# mm_robot_pcb_v5.net
KiCad netlist of a schematic drawn in EAGLE
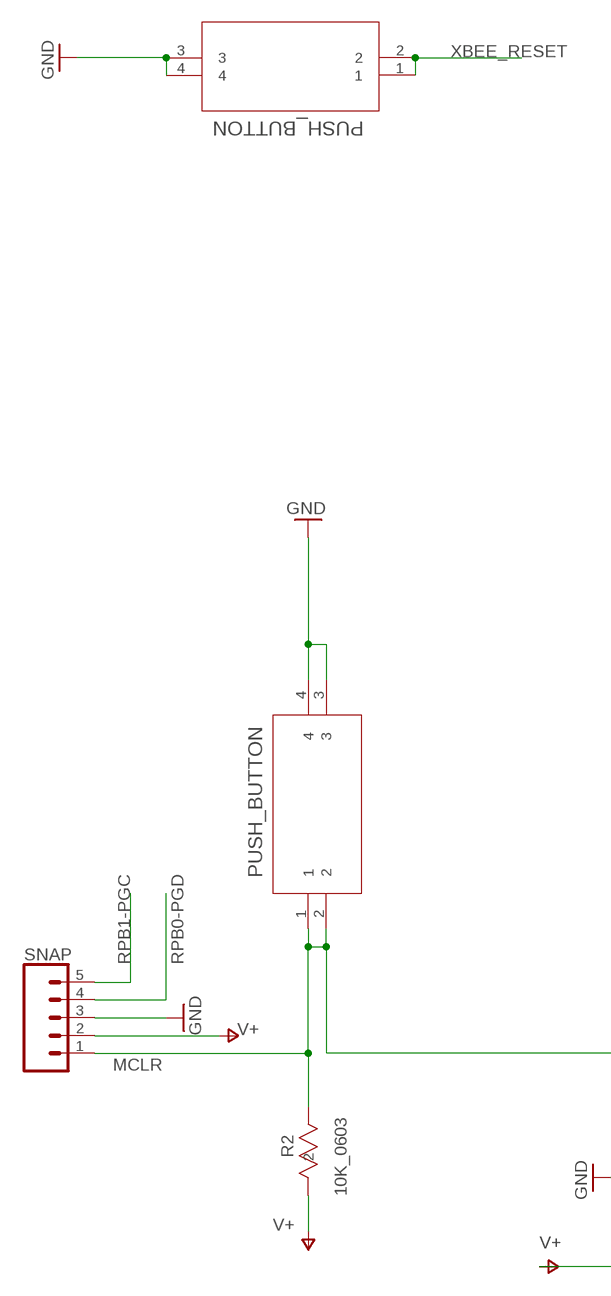
[diagram p0: schematic, sheet 1, part 1 of 2]
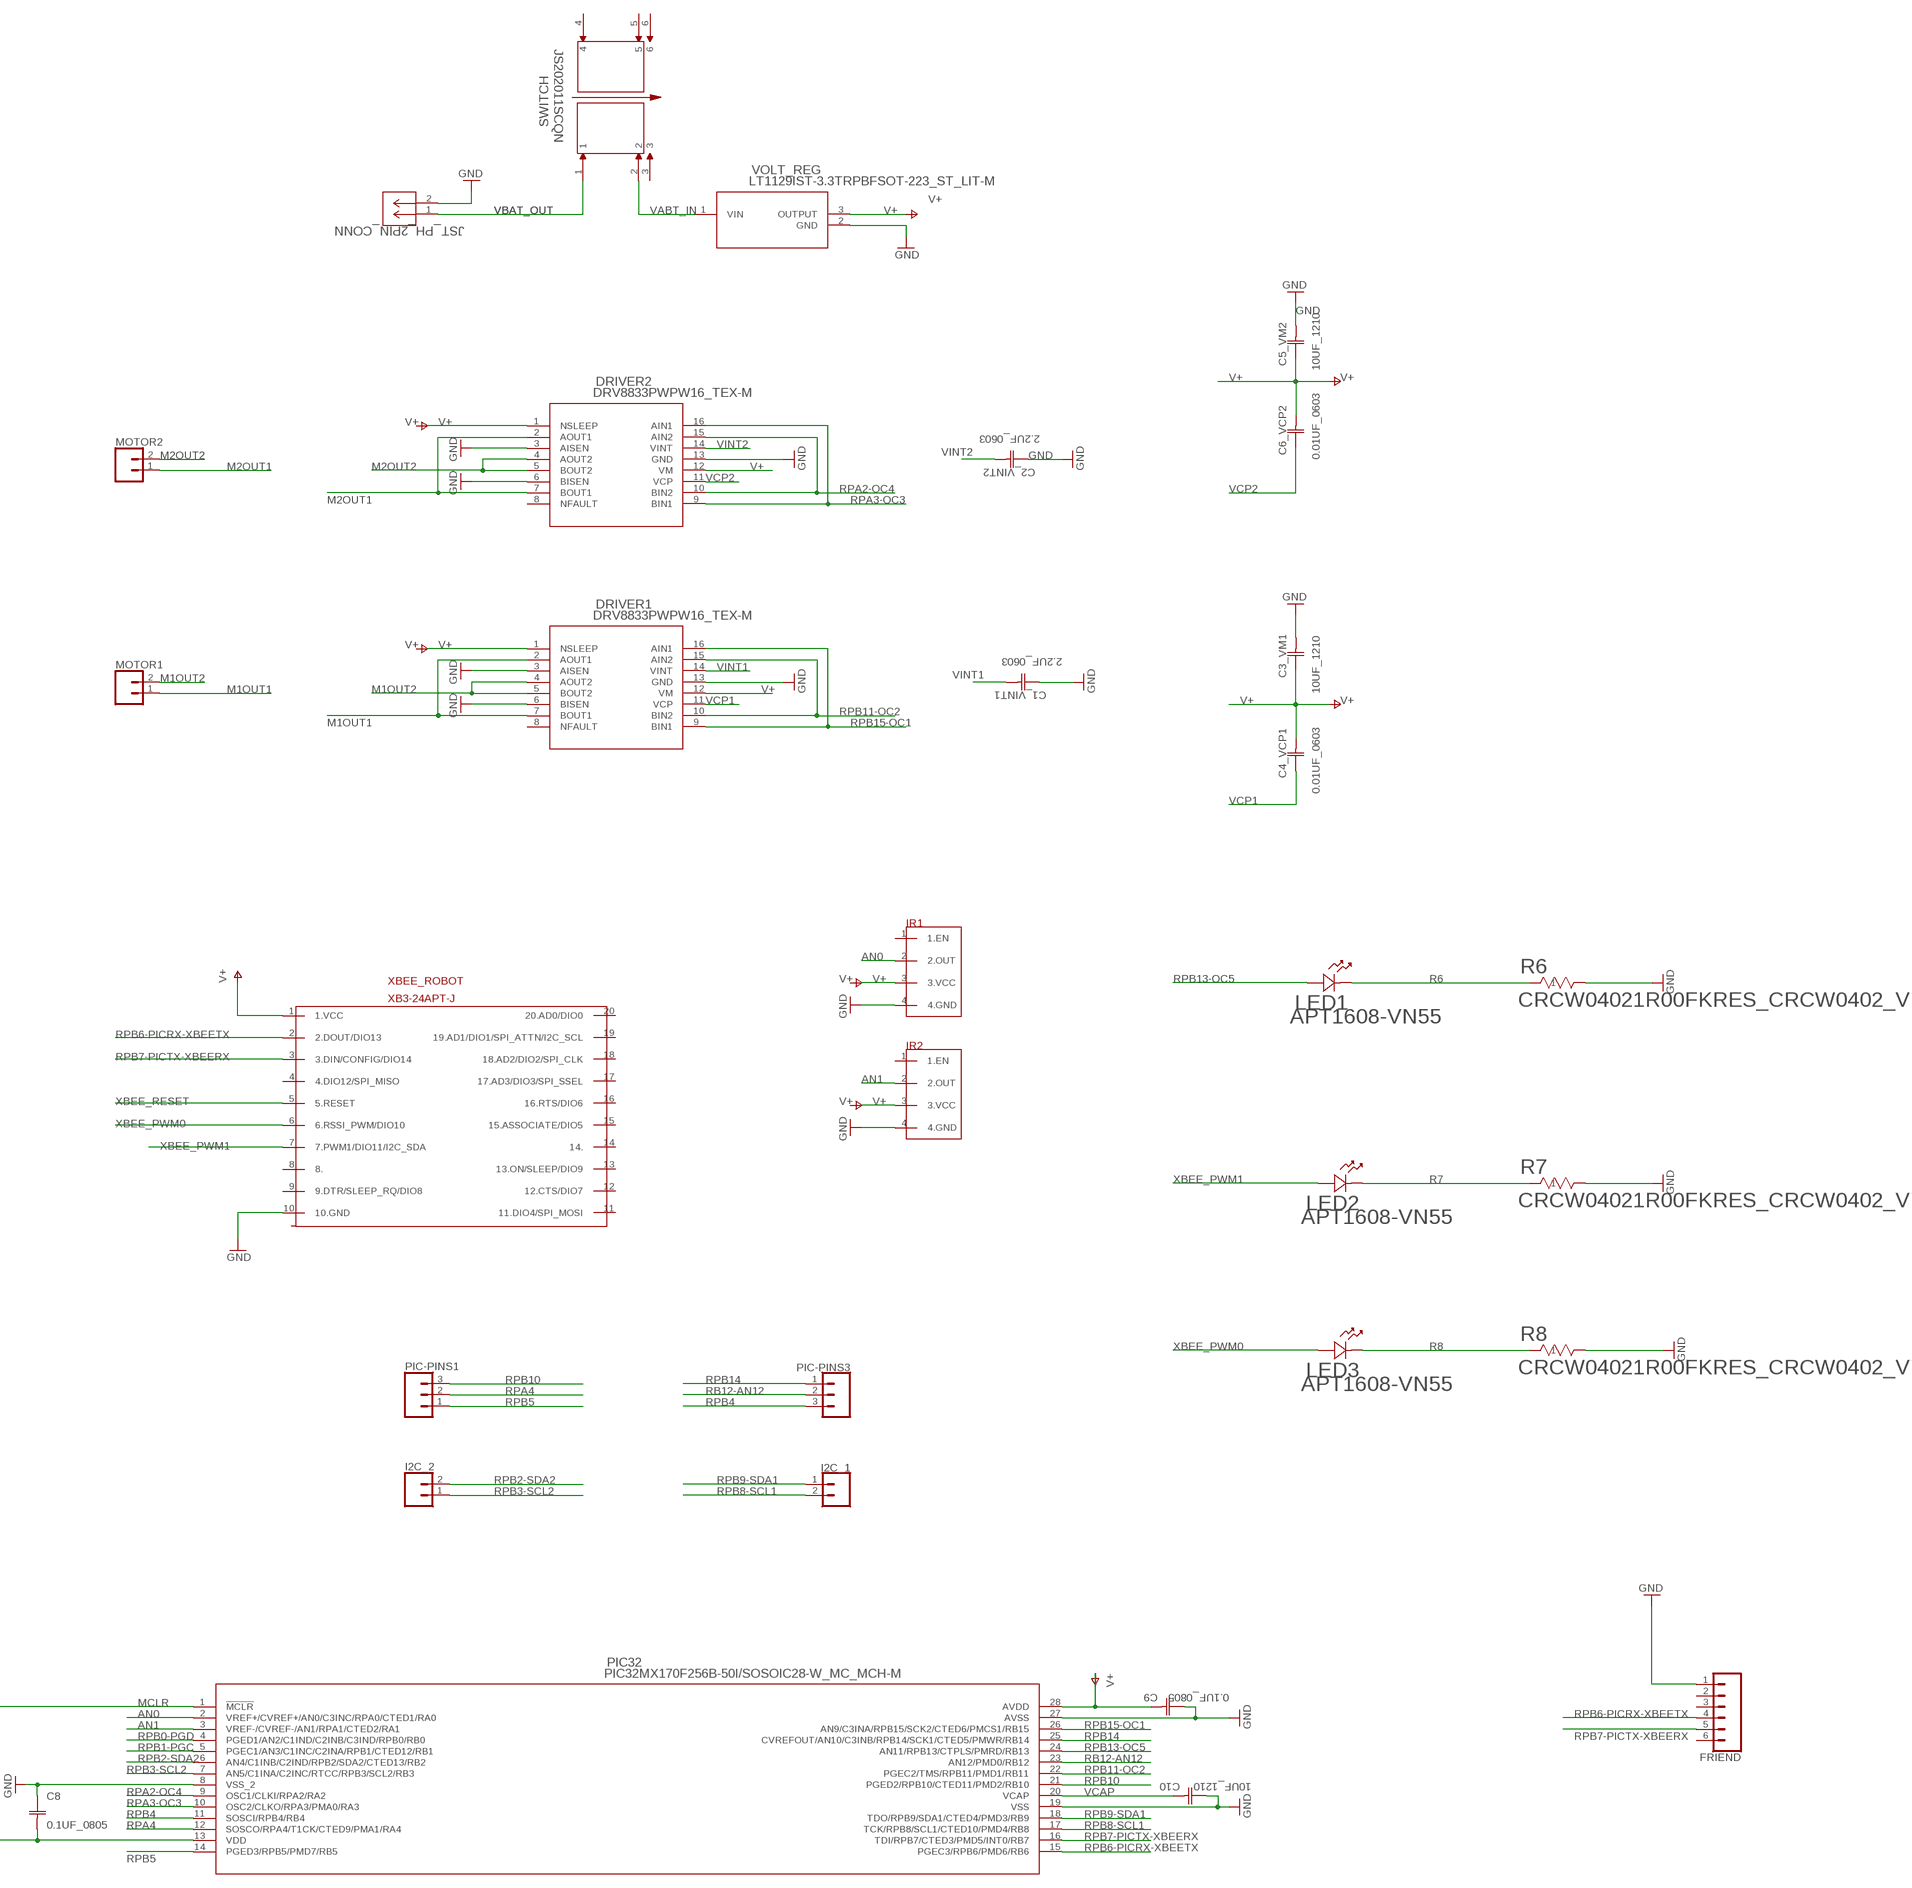
[diagram p1: schematic, sheet 1, part 2 of 2]

(export (version "E")
  (design (tool "Eeschema 10.0.6"))
  (components
    (comp (ref "C1_VINT1")
      (value "2.2UF_0603")
      (footprint "eagle-import:CAP_CL10_SAM-M")
      (fields
        (field (name "MANUFACTURER_PART_NUMBER") "CL10A225KP8NNNC")
        (field (name "COPYRIGHT") "Copyright (C) 2021 Ultra Librarian. All rights reserved.")
      )
      (libsource (lib "eagle-import") (part "CL10A225KP8NNNCCAP_CL10_SAM-M"))
    )
    (comp (ref "C2_VINT2")
      (value "2.2UF_0603")
      (footprint "eagle-import:CAP_CL10_SAM-M")
      (fields
        (field (name "MANUFACTURER_PART_NUMBER") "CL10A225KP8NNNC")
        (field (name "COPYRIGHT") "Copyright (C) 2021 Ultra Librarian. All rights reserved.")
      )
      (libsource (lib "eagle-import") (part "CL10A225KP8NNNCCAP_CL10_SAM-M"))
    )
    (comp (ref "C3_VM1")
      (value "10UF_1210")
      (footprint "eagle-import:CAP_TPS_B_AVX-M")
      (fields
        (field (name "MANUFACTURER_PART_NUMBER") "TPSB106K016R0500")
        (field (name "COPYRIGHT") "Copyright (C) 2021 Ultra Librarian. All rights reserved.")
      )
      (libsource (lib "eagle-import") (part "TPSB106K016R0500CAP_TPS_B_AVX-M"))
    )
    (comp (ref "C4_VCP1")
      (value "0.01UF_0603")
      (footprint "eagle-import:CAP_01UF_0603_X7R_G_AVX")
      (libsource (lib "eagle-import") (part "01UF_CAP"))
    )
    (comp (ref "C5_VM2")
      (value "10UF_1210")
      (footprint "eagle-import:CAP_TPS_B_AVX-M")
      (fields
        (field (name "MANUFACTURER_PART_NUMBER") "TPSB106K016R0500")
        (field (name "COPYRIGHT") "Copyright (C) 2021 Ultra Librarian. All rights reserved.")
      )
      (libsource (lib "eagle-import") (part "TPSB106K016R0500CAP_TPS_B_AVX-M"))
    )
    (comp (ref "C6_VCP2")
      (value "0.01UF_0603")
      (footprint "eagle-import:CAP_01UF_0603_X7R_G_AVX")
      (libsource (lib "eagle-import") (part "01UF_CAP"))
    )
    (comp (ref "C8")
      (value "0.1UF_0805")
      (footprint "eagle-import:CAP_C2012X7R2A104K125AA_TDK-M")
      (fields
        (field (name "MANUFACTURER_PART_NUMBER") "C2012X7R2A104K125AA")
        (field (name "COPYRIGHT") "Copyright (C) 2021 Ultra Librarian. All rights reserved.")
      )
      (libsource (lib "eagle-import") (part "C2012X7R2A104K125AACAP_C2012X7R2A104K125AA_TDK-M"))
    )
    (comp (ref "C9")
      (value "0.1UF_0805")
      (footprint "eagle-import:CAP_C2012X7R2A104K125AA_TDK-M")
      (fields
        (field (name "MANUFACTURER_PART_NUMBER") "C2012X7R2A104K125AA")
        (field (name "COPYRIGHT") "Copyright (C) 2021 Ultra Librarian. All rights reserved.")
      )
      (libsource (lib "eagle-import") (part "C2012X7R2A104K125AACAP_C2012X7R2A104K125AA_TDK-M"))
    )
    (comp (ref "C10")
      (value "10UF_1210")
      (footprint "eagle-import:CAP_TPS_B_AVX-M")
      (fields
        (field (name "MANUFACTURER_PART_NUMBER") "TPSB106K016R0500")
        (field (name "COPYRIGHT") "Copyright (C) 2021 Ultra Librarian. All rights reserved.")
      )
      (libsource (lib "eagle-import") (part "TPSB106K016R0500CAP_TPS_B_AVX-M"))
    )
    (comp (ref "DRIVER1")
      (value "DRV8833PWPW16_TEX-M")
      (footprint "eagle-import:PW16_TEX-M")
      (fields
        (field (name "MANUFACTURER_PART_NUMBER") "DRV8833PW")
        (field (name "COPYRIGHT") "Copyright (C) 2021 Ultra Librarian. All rights reserved.")
      )
      (libsource (lib "eagle-import") (part "DRV8833PWPW16_TEX-M"))
    )
    (comp (ref "DRIVER2")
      (value "DRV8833PWPW16_TEX-M")
      (footprint "eagle-import:PW16_TEX-M")
      (fields
        (field (name "MANUFACTURER_PART_NUMBER") "DRV8833PW")
        (field (name "COPYRIGHT") "Copyright (C) 2021 Ultra Librarian. All rights reserved.")
      )
      (libsource (lib "eagle-import") (part "DRV8833PWPW16_TEX-M"))
    )
    (comp (ref "FRIEND")
      (value "CONN_06NO_SILK_FEMALE_PTH")
      (footprint "eagle-import:1X06_NO_SILK")
      (libsource (lib "eagle-import") (part "CONN_06NO_SILK_FEMALE_PTH"))
    )
    (comp (ref "I2C_1")
      (value "CONN_02")
      (footprint "eagle-import:1X02")
      (libsource (lib "eagle-import") (part "CONN_02"))
    )
    (comp (ref "I2C_2")
      (value "CONN_02")
      (footprint "eagle-import:1X02")
      (libsource (lib "eagle-import") (part "CONN_02"))
    )
    (comp (ref "IR1")
      (value "GP2Y0A60SZLF")
      (footprint "eagle-import:1X04")
      (libsource (lib "eagle-import") (part "GP2Y0A60SZLF"))
    )
    (comp (ref "IR2")
      (value "GP2Y0A60SZLF")
      (footprint "eagle-import:1X04")
      (libsource (lib "eagle-import") (part "GP2Y0A60SZLF"))
    )
    (comp (ref "JST_PH_2PIN_CONN")
      (value "1769")
      (footprint "eagle-import:CONN_1769_ADA")
      (fields (field (name "COPYRIGHT") "Copyright (C) 2021 Ultra Librarian. All rights reserved."))
      (libsource (lib "eagle-import") (part "1769"))
    )
    (comp (ref "LED1")
      (value "APT1608-VN55")
      (footprint "eagle-import:LED_APT1608_KNB")
      (fields (field (name "COPYRIGHT") "Copyright (C) 2021 Ultra Librarian. All rights reserved."))
      (libsource (lib "eagle-import") (part "APT1608-VN55"))
    )
    (comp (ref "LED2")
      (value "APT1608-VN55")
      (footprint "eagle-import:LED_APT1608_KNB")
      (fields (field (name "COPYRIGHT") "Copyright (C) 2021 Ultra Librarian. All rights reserved."))
      (libsource (lib "eagle-import") (part "APT1608-VN55"))
    )
    (comp (ref "LED3")
      (value "APT1608-VN55")
      (footprint "eagle-import:LED_APT1608_KNB")
      (fields (field (name "COPYRIGHT") "Copyright (C) 2021 Ultra Librarian. All rights reserved."))
      (libsource (lib "eagle-import") (part "APT1608-VN55"))
    )
    (comp (ref "MOTOR1")
      (value "CONN_02")
      (footprint "eagle-import:1X02")
      (libsource (lib "eagle-import") (part "CONN_02"))
    )
    (comp (ref "MOTOR2")
      (value "CONN_02")
      (footprint "eagle-import:1X02")
      (libsource (lib "eagle-import") (part "CONN_02"))
    )
    (comp (ref "PIC-PINS1")
      (value "455-1750-1-ND")
      (footprint "eagle-import:1X03")
      (libsource (lib "eagle-import") (part "CONN_03"))
    )
    (comp (ref "PIC-PINS3")
      (value "455-1750-1-ND")
      (footprint "eagle-import:1X03")
      (libsource (lib "eagle-import") (part "CONN_03"))
    )
    (comp (ref "PIC32")
      (value "PIC32MX170F256B-50I/SOSOIC28-W_MC_MCH-M")
      (footprint "eagle-import:SOIC28-W_MC_MCH-M")
      (fields
        (field (name "MANUFACTURER_PART_NUMBER") "PIC32MX170F256B-50I/SO")
        (field (name "COPYRIGHT") "Copyright (C) 2021 Ultra Librarian. All rights reserved.")
      )
      (libsource (lib "eagle-import") (part "PIC32MX170F256B-50I/SOSOIC28-W_MC_MCH-M"))
    )
    (comp (ref "PIC_PB")
      (value "PUSH_BUTTON")
      (footprint "eagle-import:SMT_FS-M")
      (fields
        (field (name "MANUFACTURER_PART_NUMBER") "PTS526 SK15 SMTR2 LFS")
        (field (name "COPYRIGHT") "Copyright (C) 2021 Ultra Librarian. All rights reserved.")
      )
      (libsource (lib "eagle-import") (part "PTS526_SK15_SMTR2_LFSSMT_FS-M"))
    )
    (comp (ref "R2")
      (value "10K_0603")
      (footprint "eagle-import:RES0603_CRG_TYCO_TYC-M")
      (fields
        (field (name "MANUFACTURER_PART_NUMBER") "CRG0603F10K")
        (field (name "COPYRIGHT") "Copyright (C) 2021 Ultra Librarian. All rights reserved.")
      )
      (libsource (lib "eagle-import") (part "CRG0603F10KRES0603_CRG_TYCO_TYC-M"))
    )
    (comp (ref "R6")
      (value "CRCW04021R00FKRES_CRCW0402_VIS-M")
      (footprint "eagle-import:RES_CRCW0402_VIS-M")
      (fields
        (field (name "MANUFACTURER_PART_NUMBER") "CRCW04021R00FK")
        (field (name "COPYRIGHT") "Copyright (C) 2021 Ultra Librarian. All rights reserved.")
      )
      (libsource (lib "eagle-import") (part "CRCW04021R00FKRES_CRCW0402_VIS-M"))
    )
    (comp (ref "R7")
      (value "CRCW04021R00FKRES_CRCW0402_VIS-M")
      (footprint "eagle-import:RES_CRCW0402_VIS-M")
      (fields
        (field (name "MANUFACTURER_PART_NUMBER") "CRCW04021R00FK")
        (field (name "COPYRIGHT") "Copyright (C) 2021 Ultra Librarian. All rights reserved.")
      )
      (libsource (lib "eagle-import") (part "CRCW04021R00FKRES_CRCW0402_VIS-M"))
    )
    (comp (ref "R8")
      (value "CRCW04021R00FKRES_CRCW0402_VIS-M")
      (footprint "eagle-import:RES_CRCW0402_VIS-M")
      (fields
        (field (name "MANUFACTURER_PART_NUMBER") "CRCW04021R00FK")
        (field (name "COPYRIGHT") "Copyright (C) 2021 Ultra Librarian. All rights reserved.")
      )
      (libsource (lib "eagle-import") (part "CRCW04021R00FKRES_CRCW0402_VIS-M"))
    )
    (comp (ref "SNAP")
      (value "CONN_05")
      (footprint "eagle-import:1X05")
      (libsource (lib "eagle-import") (part "CONN_05"))
    )
    (comp (ref "SWITCH")
      (value "JS202011SCQN")
      (footprint "eagle-import:SW_JS202011SCQN")
      (fields (field (name "COPYRIGHT") "Copyright (C) 2021 Ultra Librarian. All rights reserved."))
      (libsource (lib "eagle-import") (part "JS202011SCQN"))
    )
    (comp (ref "VOLT_REG")
      (value "LT1129IST-3.3TRPBFSOT-223_ST_LIT-M")
      (footprint "eagle-import:SOT-223_ST_LIT-M")
      (fields
        (field (name "MANUFACTURER_PART_NUMBER") "LT1129IST-3.3#TRPBF")
        (field (name "COPYRIGHT") "Copyright (C) 2021 Ultra Librarian. All rights reserved.")
      )
      (libsource (lib "eagle-import") (part "LT1129IST-3.3TRPBFSOT-223_ST_LIT-M"))
    )
    (comp (ref "XBEE_PB")
      (value "PUSH_BUTTON")
      (footprint "eagle-import:SMT_FS-M")
      (fields
        (field (name "MANUFACTURER_PART_NUMBER") "PTS526 SK15 SMTR2 LFS")
        (field (name "COPYRIGHT") "Copyright (C) 2021 Ultra Librarian. All rights reserved.")
      )
      (libsource (lib "eagle-import") (part "PTS526_SK15_SMTR2_LFSSMT_FS-M"))
    )
    (comp (ref "XBEE_ROBOT")
      (value "XB3-24APT-J")
      (footprint "eagle-import:XB3-24APT-J")
      (libsource (lib "eagle-import") (part "XB3-24APT-J"))
    )
  )
  (nets
    (net (code "1") (name "/AN0") (class "Default")
      (node (ref "IR1") (pin "2") (pinfunction "2.OUT_2") (pintype "bidirectional"))
      (node (ref "PIC32") (pin "2") (pinfunction "VREF+/CVREF+/AN0/C3INC/RPA0/CTED1/RA0_2") (pintype "bidirectional"))
    )
    (net (code "2") (name "/AN1") (class "Default")
      (node (ref "IR2") (pin "2") (pinfunction "2.OUT_2") (pintype "bidirectional"))
      (node (ref "PIC32") (pin "3") (pinfunction "VREF-/CVREF-/AN1/RPA1/CTED2/RA1_3") (pintype "bidirectional"))
    )
    (net (code "3") (name "/M1OUT1") (class "Default")
      (node (ref "DRIVER1") (pin "2") (pinfunction "AOUT1_2") (pintype "output"))
      (node (ref "DRIVER1") (pin "7") (pinfunction "BOUT1_7") (pintype "output"))
      (node (ref "MOTOR1") (pin "1") (pinfunction "1_1") (pintype "passive"))
    )
    (net (code "4") (name "/M1OUT2") (class "Default")
      (node (ref "DRIVER1") (pin "4") (pinfunction "AOUT2_4") (pintype "output"))
      (node (ref "DRIVER1") (pin "5") (pinfunction "BOUT2_5") (pintype "output"))
      (node (ref "MOTOR1") (pin "2") (pinfunction "2_2") (pintype "passive"))
    )
    (net (code "5") (name "/M2OUT1") (class "Default")
      (node (ref "DRIVER2") (pin "2") (pinfunction "AOUT1_2") (pintype "output"))
      (node (ref "DRIVER2") (pin "7") (pinfunction "BOUT1_7") (pintype "output"))
      (node (ref "MOTOR2") (pin "1") (pinfunction "1_1") (pintype "passive"))
    )
    (net (code "6") (name "/M2OUT2") (class "Default")
      (node (ref "DRIVER2") (pin "4") (pinfunction "AOUT2_4") (pintype "output"))
      (node (ref "DRIVER2") (pin "5") (pinfunction "BOUT2_5") (pintype "output"))
      (node (ref "MOTOR2") (pin "2") (pinfunction "2_2") (pintype "passive"))
    )
    (net (code "7") (name "/MCLR") (class "Default")
      (node (ref "PIC32") (pin "1") (pinfunction "~{MCLR}_1") (pintype "bidirectional"))
      (node (ref "PIC_PB") (pin "1") (pinfunction "1_1") (pintype "passive"))
      (node (ref "PIC_PB") (pin "2") (pinfunction "2_2") (pintype "passive"))
      (node (ref "R2") (pin "1") (pinfunction "1_1") (pintype "passive"))
      (node (ref "SNAP") (pin "1") (pinfunction "1_1") (pintype "passive"))
    )
    (net (code "8") (name "/R6") (class "Default")
      (node (ref "LED1") (pin "1") (pinfunction "1_1") (pintype "passive"))
      (node (ref "R6") (pin "1") (pinfunction "1_1") (pintype "passive"))
    )
    (net (code "9") (name "/R7") (class "Default")
      (node (ref "LED2") (pin "1") (pinfunction "1_1") (pintype "passive"))
      (node (ref "R7") (pin "1") (pinfunction "1_1") (pintype "passive"))
    )
    (net (code "10") (name "/R8") (class "Default")
      (node (ref "LED3") (pin "1") (pinfunction "1_1") (pintype "passive"))
      (node (ref "R8") (pin "1") (pinfunction "1_1") (pintype "passive"))
    )
    (net (code "11") (name "/RB12-AN12") (class "Default")
      (node (ref "PIC-PINS3") (pin "2") (pinfunction "2_2") (pintype "passive"))
      (node (ref "PIC32") (pin "23") (pinfunction "AN12/PMD0/RB12_23") (pintype "bidirectional"))
    )
    (net (code "12") (name "/RPA2-OC4") (class "Default")
      (node (ref "DRIVER2") (pin "10") (pinfunction "BIN2_10") (pintype "input"))
      (node (ref "DRIVER2") (pin "15") (pinfunction "AIN2_15") (pintype "input"))
      (node (ref "PIC32") (pin "9") (pinfunction "OSC1/CLKI/RPA2/RA2_9") (pintype "bidirectional"))
    )
    (net (code "13") (name "/RPA3-OC3") (class "Default")
      (node (ref "DRIVER2") (pin "16") (pinfunction "AIN1_16") (pintype "input"))
      (node (ref "DRIVER2") (pin "9") (pinfunction "BIN1_9") (pintype "input"))
      (node (ref "PIC32") (pin "10") (pinfunction "OSC2/CLKO/RPA3/PMA0/RA3_10") (pintype "bidirectional"))
    )
    (net (code "14") (name "/RPA4") (class "Default")
      (node (ref "PIC-PINS1") (pin "2") (pinfunction "2_2") (pintype "passive"))
      (node (ref "PIC32") (pin "12") (pinfunction "SOSCO/RPA4/T1CK/CTED9/PMA1/RA4_12") (pintype "bidirectional"))
    )
    (net (code "15") (name "/RPB0-PGD") (class "Default")
      (node (ref "PIC32") (pin "4") (pinfunction "PGED1/AN2/C1IND/C2INB/C3IND/RPB0/RB0_4") (pintype "bidirectional"))
      (node (ref "SNAP") (pin "4") (pinfunction "4_4") (pintype "passive"))
    )
    (net (code "16") (name "/RPB1-PGC") (class "Default")
      (node (ref "PIC32") (pin "5") (pinfunction "PGEC1/AN3/C1INC/C2INA/RPB1/CTED12/RB1_5") (pintype "bidirectional"))
      (node (ref "SNAP") (pin "5") (pinfunction "5_5") (pintype "passive"))
    )
    (net (code "17") (name "/RPB2-SDA2") (class "Default")
      (node (ref "I2C_2") (pin "2") (pinfunction "2_2") (pintype "passive"))
      (node (ref "PIC32") (pin "6") (pinfunction "AN4/C1INB/C2IND/RPB2/SDA2/CTED13/RB2_6") (pintype "bidirectional"))
    )
    (net (code "18") (name "/RPB3-SCL2") (class "Default")
      (node (ref "I2C_2") (pin "1") (pinfunction "1_1") (pintype "passive"))
      (node (ref "PIC32") (pin "7") (pinfunction "AN5/C1INA/C2INC/RTCC/RPB3/SCL2/RB3_7") (pintype "bidirectional"))
    )
    (net (code "19") (name "/RPB4") (class "Default")
      (node (ref "PIC-PINS3") (pin "3") (pinfunction "3_3") (pintype "passive"))
      (node (ref "PIC32") (pin "11") (pinfunction "SOSCI/RPB4/RB4_11") (pintype "bidirectional"))
    )
    (net (code "20") (name "/RPB5") (class "Default")
      (node (ref "PIC-PINS1") (pin "1") (pinfunction "1_1") (pintype "passive"))
      (node (ref "PIC32") (pin "14") (pinfunction "PGED3/RPB5/PMD7/RB5_14") (pintype "bidirectional"))
    )
    (net (code "21") (name "/RPB6-PICRX-XBEETX") (class "Default")
      (node (ref "FRIEND") (pin "4") (pinfunction "4_4") (pintype "passive"))
      (node (ref "PIC32") (pin "15") (pinfunction "PGEC3/RPB6/PMD6/RB6_15") (pintype "bidirectional"))
      (node (ref "XBEE_ROBOT") (pin "2") (pinfunction "2.DOUT/DIO13_2") (pintype "bidirectional"))
    )
    (net (code "22") (name "/RPB7-PICTX-XBEERX") (class "Default")
      (node (ref "FRIEND") (pin "5") (pinfunction "5_5") (pintype "passive"))
      (node (ref "PIC32") (pin "16") (pinfunction "TDI/RPB7/CTED3/PMD5/INT0/RB7_16") (pintype "bidirectional"))
      (node (ref "XBEE_ROBOT") (pin "3") (pinfunction "3.DIN/CONFIG/DIO14_3") (pintype "bidirectional"))
    )
    (net (code "23") (name "/RPB8-SCL1") (class "Default")
      (node (ref "I2C_1") (pin "2") (pinfunction "2_2") (pintype "passive"))
      (node (ref "PIC32") (pin "17") (pinfunction "TCK/RPB8/SCL1/CTED10/PMD4/RB8_17") (pintype "bidirectional"))
    )
    (net (code "24") (name "/RPB9-SDA1") (class "Default")
      (node (ref "I2C_1") (pin "1") (pinfunction "1_1") (pintype "passive"))
      (node (ref "PIC32") (pin "18") (pinfunction "TDO/RPB9/SDA1/CTED4/PMD3/RB9_18") (pintype "bidirectional"))
    )
    (net (code "25") (name "/RPB10") (class "Default")
      (node (ref "PIC-PINS1") (pin "3") (pinfunction "3_3") (pintype "passive"))
      (node (ref "PIC32") (pin "21") (pinfunction "PGED2/RPB10/CTED11/PMD2/RB10_21") (pintype "bidirectional"))
    )
    (net (code "26") (name "/RPB11-OC2") (class "Default")
      (node (ref "DRIVER1") (pin "10") (pinfunction "BIN2_10") (pintype "input"))
      (node (ref "DRIVER1") (pin "15") (pinfunction "AIN2_15") (pintype "input"))
      (node (ref "PIC32") (pin "22") (pinfunction "PGEC2/TMS/RPB11/PMD1/RB11_22") (pintype "bidirectional"))
    )
    (net (code "27") (name "/RPB13-OC5") (class "Default")
      (node (ref "LED1") (pin "2") (pinfunction "2_2") (pintype "passive"))
      (node (ref "PIC32") (pin "24") (pinfunction "AN11/RPB13/CTPLS/PMRD/RB13_24") (pintype "bidirectional"))
    )
    (net (code "28") (name "/RPB14") (class "Default")
      (node (ref "PIC-PINS3") (pin "1") (pinfunction "1_1") (pintype "passive"))
      (node (ref "PIC32") (pin "25") (pinfunction "CVREFOUT/AN10/C3INB/RPB14/SCK1/CTED5/PMWR/RB14_25") (pintype "bidirectional"))
    )
    (net (code "29") (name "/RPB15-OC1") (class "Default")
      (node (ref "DRIVER1") (pin "16") (pinfunction "AIN1_16") (pintype "input"))
      (node (ref "DRIVER1") (pin "9") (pinfunction "BIN1_9") (pintype "input"))
      (node (ref "PIC32") (pin "26") (pinfunction "AN9/C3INA/RPB15/SCK2/CTED6/PMCS1/RB15_26") (pintype "bidirectional"))
    )
    (net (code "30") (name "/VABT_IN") (class "Default")
      (node (ref "SWITCH") (pin "2") (pinfunction "2_2") (pintype "passive"))
      (node (ref "VOLT_REG") (pin "1") (pinfunction "VIN_1") (pintype "input"))
    )
    (net (code "31") (name "/VBAT_OUT") (class "Default")
      (node (ref "JST_PH_2PIN_CONN") (pin "1") (pinfunction "1_1") (pintype "passive"))
      (node (ref "SWITCH") (pin "1") (pinfunction "1_1") (pintype "passive"))
    )
    (net (code "32") (name "/VCAP") (class "Default")
      (node (ref "C10") (pin "2") (pinfunction "12_2") (pintype "passive"))
      (node (ref "PIC32") (pin "20") (pinfunction "VCAP_20") (pintype "power_in"))
    )
    (net (code "33") (name "/VCP1") (class "Default")
      (node (ref "C4_VCP1") (pin "1") (pinfunction "1_1") (pintype "passive"))
      (node (ref "DRIVER1") (pin "11") (pinfunction "VCP_11") (pintype "bidirectional"))
    )
    (net (code "34") (name "/VCP2") (class "Default")
      (node (ref "C6_VCP2") (pin "1") (pinfunction "1_1") (pintype "passive"))
      (node (ref "DRIVER2") (pin "11") (pinfunction "VCP_11") (pintype "bidirectional"))
    )
    (net (code "35") (name "/VINT1") (class "Default")
      (node (ref "C1_VINT1") (pin "2") (pinfunction "2_2") (pintype "passive"))
      (node (ref "DRIVER1") (pin "14") (pinfunction "VINT_14") (pintype "passive"))
    )
    (net (code "36") (name "/VINT2") (class "Default")
      (node (ref "C2_VINT2") (pin "2") (pinfunction "2_2") (pintype "passive"))
      (node (ref "DRIVER2") (pin "14") (pinfunction "VINT_14") (pintype "passive"))
    )
    (net (code "37") (name "/XBEE_PWM0") (class "Default")
      (node (ref "LED3") (pin "2") (pinfunction "2_2") (pintype "passive"))
      (node (ref "XBEE_ROBOT") (pin "6") (pinfunction "6.RSSI_PWM/DIO10_6") (pintype "bidirectional"))
    )
    (net (code "38") (name "/XBEE_PWM1") (class "Default")
      (node (ref "LED2") (pin "2") (pinfunction "2_2") (pintype "passive"))
      (node (ref "XBEE_ROBOT") (pin "7") (pinfunction "7.PWM1/DIO11/I2C_SDA_7") (pintype "bidirectional"))
    )
    (net (code "39") (name "/XBEE_RESET") (class "Default")
      (node (ref "XBEE_PB") (pin "1") (pinfunction "1_1") (pintype "passive"))
      (node (ref "XBEE_PB") (pin "2") (pinfunction "2_2") (pintype "passive"))
      (node (ref "XBEE_ROBOT") (pin "5") (pinfunction "5.RESET_5") (pintype "bidirectional"))
    )
    (net (code "40") (name "GND") (class "Default")
      (node (ref "C10") (pin "1") (pinfunction "11_1") (pintype "passive"))
      (node (ref "C1_VINT1") (pin "1") (pinfunction "1_1") (pintype "passive"))
      (node (ref "C2_VINT2") (pin "1") (pinfunction "1_1") (pintype "passive"))
      (node (ref "C3_VM1") (pin "2") (pinfunction "12_2") (pintype "passive"))
      (node (ref "C5_VM2") (pin "2") (pinfunction "12_2") (pintype "passive"))
      (node (ref "C8") (pin "1") (pinfunction "1_1") (pintype "passive"))
      (node (ref "C9") (pin "1") (pinfunction "1_1") (pintype "passive"))
      (node (ref "DRIVER1") (pin "13") (pinfunction "GND_13") (pintype "power_in"))
      (node (ref "DRIVER1") (pin "3") (pinfunction "AISEN_3") (pintype "bidirectional"))
      (node (ref "DRIVER1") (pin "6") (pinfunction "BISEN_6") (pintype "bidirectional"))
      (node (ref "DRIVER2") (pin "13") (pinfunction "GND_13") (pintype "power_in"))
      (node (ref "DRIVER2") (pin "3") (pinfunction "AISEN_3") (pintype "bidirectional"))
      (node (ref "DRIVER2") (pin "6") (pinfunction "BISEN_6") (pintype "bidirectional"))
      (node (ref "FRIEND") (pin "1") (pinfunction "1_1") (pintype "passive"))
      (node (ref "IR1") (pin "4") (pinfunction "4.GND_4") (pintype "bidirectional"))
      (node (ref "IR2") (pin "4") (pinfunction "4.GND_4") (pintype "bidirectional"))
      (node (ref "JST_PH_2PIN_CONN") (pin "2") (pinfunction "2_2") (pintype "passive"))
      (node (ref "PIC32") (pin "19") (pinfunction "VSS_19") (pintype "power_in"))
      (node (ref "PIC32") (pin "27") (pinfunction "AVSS_27") (pintype "power_in"))
      (node (ref "PIC32") (pin "8") (pinfunction "VSS_2_8") (pintype "power_in"))
      (node (ref "PIC_PB") (pin "3") (pinfunction "3_3") (pintype "passive"))
      (node (ref "PIC_PB") (pin "4") (pinfunction "4_4") (pintype "passive"))
      (node (ref "R6") (pin "2") (pinfunction "2_2") (pintype "passive"))
      (node (ref "R7") (pin "2") (pinfunction "2_2") (pintype "passive"))
      (node (ref "R8") (pin "2") (pinfunction "2_2") (pintype "passive"))
      (node (ref "SNAP") (pin "3") (pinfunction "3_3") (pintype "passive"))
      (node (ref "VOLT_REG") (pin "2") (pinfunction "GND_2") (pintype "power_in"))
      (node (ref "XBEE_PB") (pin "3") (pinfunction "3_3") (pintype "passive"))
      (node (ref "XBEE_PB") (pin "4") (pinfunction "4_4") (pintype "passive"))
      (node (ref "XBEE_ROBOT") (pin "10") (pinfunction "10.GND_10") (pintype "bidirectional"))
    )
    (net (code "41") (name "V+") (class "Default")
      (node (ref "C3_VM1") (pin "1") (pinfunction "11_1") (pintype "passive"))
      (node (ref "C4_VCP1") (pin "2") (pinfunction "2_2") (pintype "passive"))
      (node (ref "C5_VM2") (pin "1") (pinfunction "11_1") (pintype "passive"))
      (node (ref "C6_VCP2") (pin "2") (pinfunction "2_2") (pintype "passive"))
      (node (ref "C8") (pin "2") (pinfunction "2_2") (pintype "passive"))
      (node (ref "C9") (pin "2") (pinfunction "2_2") (pintype "passive"))
      (node (ref "DRIVER1") (pin "1") (pinfunction "NSLEEP_1") (pintype "input"))
      (node (ref "DRIVER1") (pin "12") (pinfunction "VM_12") (pintype "power_in"))
      (node (ref "DRIVER2") (pin "1") (pinfunction "NSLEEP_1") (pintype "input"))
      (node (ref "DRIVER2") (pin "12") (pinfunction "VM_12") (pintype "power_in"))
      (node (ref "IR1") (pin "3") (pinfunction "3.VCC_3") (pintype "bidirectional"))
      (node (ref "IR2") (pin "3") (pinfunction "3.VCC_3") (pintype "bidirectional"))
      (node (ref "PIC32") (pin "13") (pinfunction "VDD_13") (pintype "power_in"))
      (node (ref "PIC32") (pin "28") (pinfunction "AVDD_28") (pintype "power_in"))
      (node (ref "R2") (pin "2") (pinfunction "2_2") (pintype "passive"))
      (node (ref "SNAP") (pin "2") (pinfunction "2_2") (pintype "passive"))
      (node (ref "VOLT_REG") (pin "3") (pinfunction "OUTPUT_3") (pintype "output"))
      (node (ref "XBEE_ROBOT") (pin "1") (pinfunction "1.VCC_1") (pintype "bidirectional"))
    )
    (net (code "42") (name "unconnected-(DRIVER1-NFAULT-Pad8)") (class "Default")
      (node (ref "DRIVER1") (pin "8") (pinfunction "NFAULT_8") (pintype "output"))
    )
    (net (code "43") (name "unconnected-(DRIVER2-NFAULT-Pad8)") (class "Default")
      (node (ref "DRIVER2") (pin "8") (pinfunction "NFAULT_8") (pintype "output"))
    )
    (net (code "44") (name "unconnected-(FRIEND-Pad2)") (class "Default")
      (node (ref "FRIEND") (pin "2") (pinfunction "2_2") (pintype "passive"))
    )
    (net (code "45") (name "unconnected-(FRIEND-Pad3)") (class "Default")
      (node (ref "FRIEND") (pin "3") (pinfunction "3_3") (pintype "passive"))
    )
    (net (code "46") (name "unconnected-(FRIEND-Pad6)") (class "Default")
      (node (ref "FRIEND") (pin "6") (pinfunction "6_6") (pintype "passive"))
    )
    (net (code "47") (name "unconnected-(IR1-1.EN-Pad1)") (class "Default")
      (node (ref "IR1") (pin "1") (pinfunction "1.EN_1") (pintype "bidirectional"))
    )
    (net (code "48") (name "unconnected-(IR2-1.EN-Pad1)") (class "Default")
      (node (ref "IR2") (pin "1") (pinfunction "1.EN_1") (pintype "bidirectional"))
    )
    (net (code "49") (name "unconnected-(SWITCH-Pad3)") (class "Default")
      (node (ref "SWITCH") (pin "3") (pinfunction "3_3") (pintype "passive"))
    )
    (net (code "50") (name "unconnected-(SWITCH-Pad4)") (class "Default")
      (node (ref "SWITCH") (pin "4") (pinfunction "4_4") (pintype "passive"))
    )
    (net (code "51") (name "unconnected-(SWITCH-Pad5)") (class "Default")
      (node (ref "SWITCH") (pin "5") (pinfunction "5_5") (pintype "passive"))
    )
    (net (code "52") (name "unconnected-(SWITCH-Pad6)") (class "Default")
      (node (ref "SWITCH") (pin "6") (pinfunction "6_6") (pintype "passive"))
    )
    (net (code "53") (name "unconnected-(XBEE_ROBOT-4.DIO12{slash}SPI_MISO-Pad4)") (class "Default")
      (node (ref "XBEE_ROBOT") (pin "4") (pinfunction "4.DIO12/SPI_MISO_4") (pintype "bidirectional"))
    )
    (net (code "54") (name "unconnected-(XBEE_ROBOT-8.-Pad8)") (class "Default")
      (node (ref "XBEE_ROBOT") (pin "8") (pinfunction "8._8") (pintype "bidirectional"))
    )
    (net (code "55") (name "unconnected-(XBEE_ROBOT-9.DTR{slash}SLEEP_RQ{slash}DIO8-Pad9)") (class "Default")
      (node (ref "XBEE_ROBOT") (pin "9") (pinfunction "9.DTR/SLEEP_RQ/DIO8_9") (pintype "bidirectional"))
    )
    (net (code "56") (name "unconnected-(XBEE_ROBOT-11.DIO4{slash}SPI_MOSI-Pad11)") (class "Default")
      (node (ref "XBEE_ROBOT") (pin "11") (pinfunction "11.DIO4/SPI_MOSI_11") (pintype "bidirectional"))
    )
    (net (code "57") (name "unconnected-(XBEE_ROBOT-12.CTS{slash}DIO7-Pad12)") (class "Default")
      (node (ref "XBEE_ROBOT") (pin "12") (pinfunction "12.CTS/DIO7_12") (pintype "bidirectional"))
    )
    (net (code "58") (name "unconnected-(XBEE_ROBOT-13.ON{slash}SLEEP{slash}DIO9-Pad13)") (class "Default")
      (node (ref "XBEE_ROBOT") (pin "13") (pinfunction "13.ON/SLEEP/DIO9_13") (pintype "bidirectional"))
    )
    (net (code "59") (name "unconnected-(XBEE_ROBOT-14.-Pad14)") (class "Default")
      (node (ref "XBEE_ROBOT") (pin "14") (pinfunction "14._14") (pintype "bidirectional"))
    )
    (net (code "60") (name "unconnected-(XBEE_ROBOT-15.ASSOCIATE{slash}DIO5-Pad15)") (class "Default")
      (node (ref "XBEE_ROBOT") (pin "15") (pinfunction "15.ASSOCIATE/DIO5_15") (pintype "bidirectional"))
    )
    (net (code "61") (name "unconnected-(XBEE_ROBOT-16.RTS{slash}DIO6-Pad16)") (class "Default")
      (node (ref "XBEE_ROBOT") (pin "16") (pinfunction "16.RTS/DIO6_16") (pintype "bidirectional"))
    )
    (net (code "62") (name "unconnected-(XBEE_ROBOT-17.AD3{slash}DIO3{slash}SPI_SSEL-Pad17)") (class "Default")
      (node (ref "XBEE_ROBOT") (pin "17") (pinfunction "17.AD3/DIO3/SPI_SSEL_17") (pintype "bidirectional"))
    )
    (net (code "63") (name "unconnected-(XBEE_ROBOT-18.AD2{slash}DIO2{slash}SPI_CLK-Pad18)") (class "Default")
      (node (ref "XBEE_ROBOT") (pin "18") (pinfunction "18.AD2/DIO2/SPI_CLK_18") (pintype "bidirectional"))
    )
    (net (code "64") (name "unconnected-(XBEE_ROBOT-19.AD1{slash}DIO1{slash}SPI_ATTN{slash}I2C_SCL-Pad19)") (class "Default")
      (node (ref "XBEE_ROBOT") (pin "19") (pinfunction "19.AD1/DIO1/SPI_ATTN/I2C_SCL_19") (pintype "bidirectional"))
    )
    (net (code "65") (name "unconnected-(XBEE_ROBOT-20.AD0{slash}DIO0-Pad20)") (class "Default")
      (node (ref "XBEE_ROBOT") (pin "20") (pinfunction "20.AD0/DIO0_20") (pintype "bidirectional"))
    )
  )
)
